# shinobi.net
KiCad netlist of a schematic drawn in EAGLE
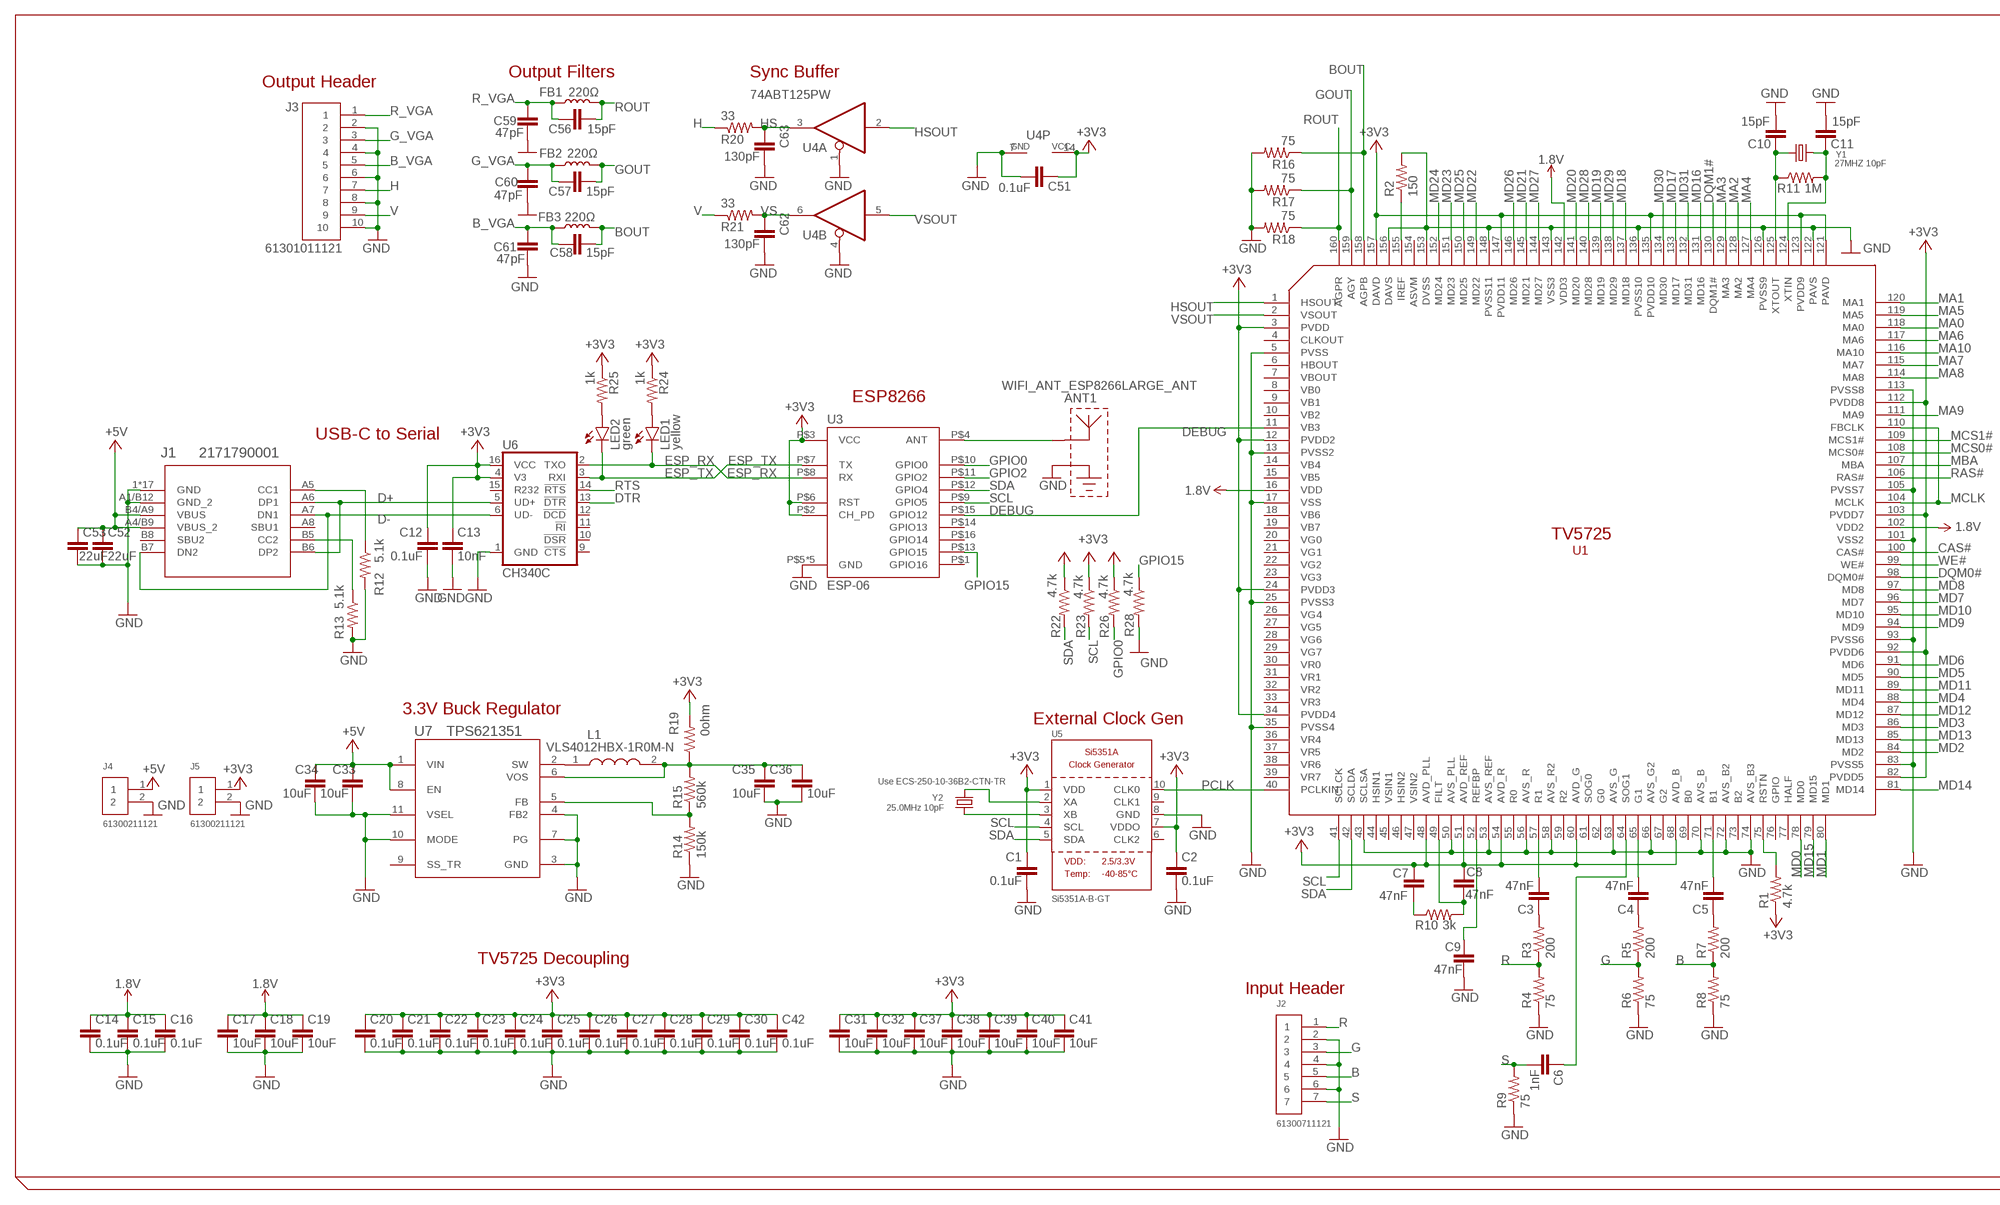
[diagram p0: schematic, sheet 1, part 1 of 2]
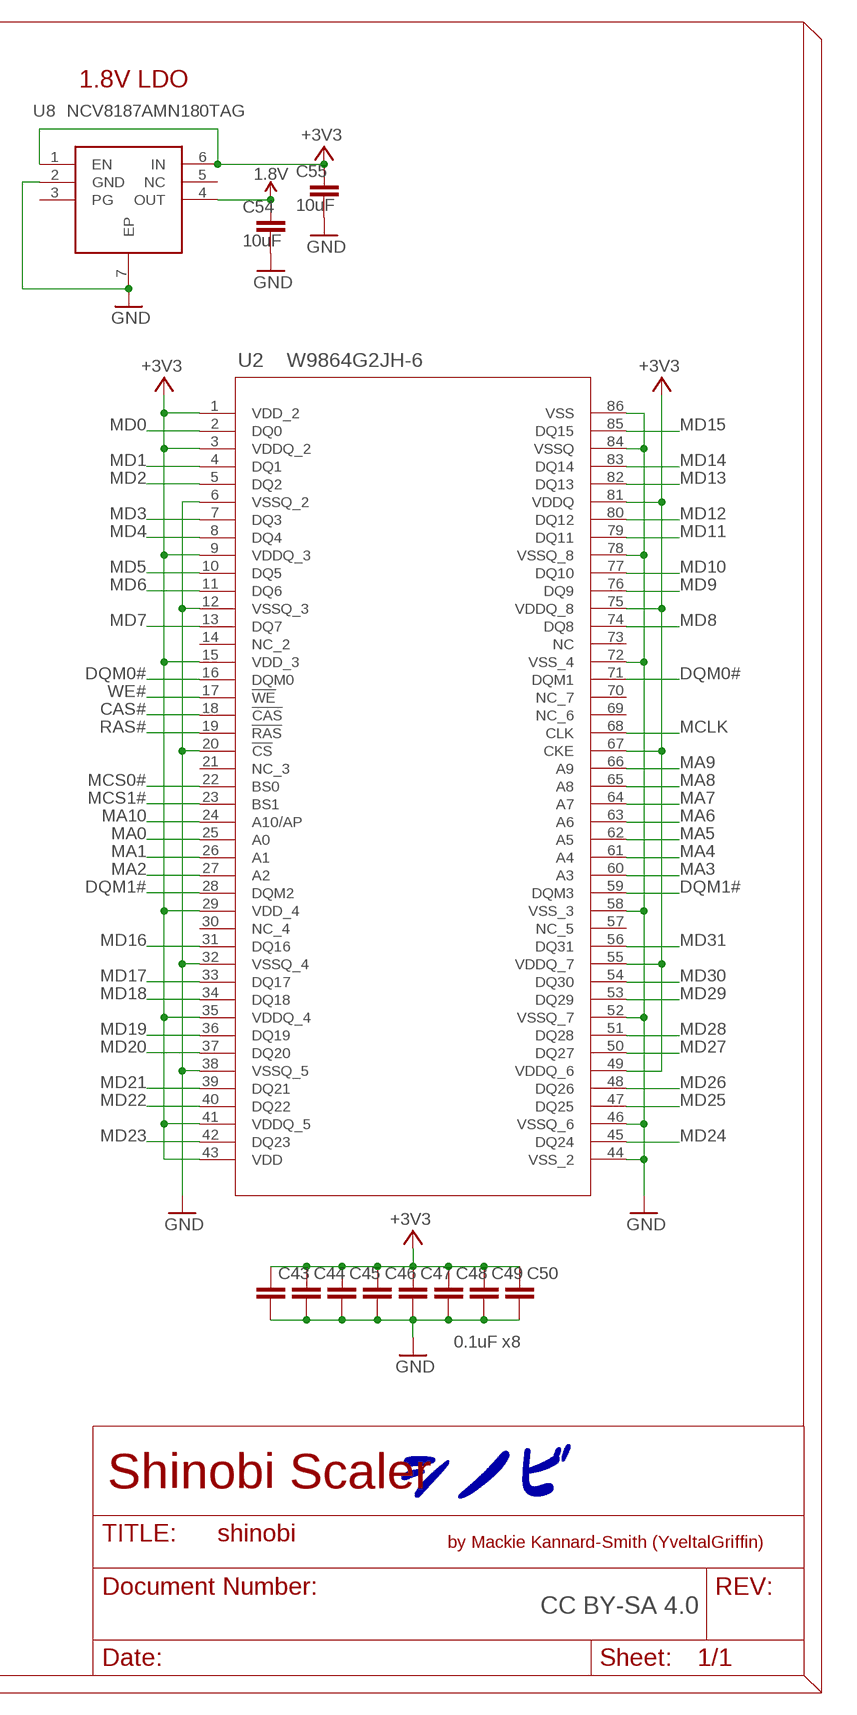
[diagram p1: schematic, sheet 1, part 2 of 2]

(export (version "E")
  (design (tool "Eeschema 10.0.6"))
  (components
    (comp (ref "ANT1")
      (value "WIFI_ANT_ESP8266LARGE_ANT")
      (footprint "eagle-import:ANTENNA")
      (libsource (lib "eagle-import") (part "WIFI_ANT_ESP8266LARGE_ANT"))
    )
    (comp (ref "C1")
      (value "0.1uF")
      (footprint "eagle-import:C0402")
      (libsource (lib "eagle-import") (part "C-USC0402"))
    )
    (comp (ref "C2")
      (value "0.1uF")
      (footprint "eagle-import:C0402")
      (libsource (lib "eagle-import") (part "C-USC0402"))
    )
    (comp (ref "C3")
      (value "47nF")
      (footprint "eagle-import:C0402")
      (libsource (lib "eagle-import") (part "C-USC0402"))
    )
    (comp (ref "C4")
      (value "47nF")
      (footprint "eagle-import:C0402")
      (libsource (lib "eagle-import") (part "C-USC0402"))
    )
    (comp (ref "C5")
      (value "47nF")
      (footprint "eagle-import:C0402")
      (libsource (lib "eagle-import") (part "C-USC0402"))
    )
    (comp (ref "C6")
      (value "1nF")
      (footprint "eagle-import:C0402")
      (libsource (lib "eagle-import") (part "C-USC0402"))
    )
    (comp (ref "C7")
      (value "47nF")
      (footprint "eagle-import:C0402")
      (libsource (lib "eagle-import") (part "C-USC0402"))
    )
    (comp (ref "C8")
      (value "47nF")
      (footprint "eagle-import:C0402")
      (libsource (lib "eagle-import") (part "C-USC0402"))
    )
    (comp (ref "C9")
      (value "47nF")
      (footprint "eagle-import:C0402")
      (libsource (lib "eagle-import") (part "C-USC0402"))
    )
    (comp (ref "C10")
      (value "15pF")
      (footprint "eagle-import:C0402")
      (libsource (lib "eagle-import") (part "C-USC0402"))
    )
    (comp (ref "C11")
      (value "15pF")
      (footprint "eagle-import:C0402")
      (libsource (lib "eagle-import") (part "C-USC0402"))
    )
    (comp (ref "C12")
      (value "0.1uF")
      (footprint "eagle-import:C0402")
      (libsource (lib "eagle-import") (part "C-USC0402"))
    )
    (comp (ref "C13")
      (value "10nF")
      (footprint "eagle-import:C0402")
      (libsource (lib "eagle-import") (part "C-USC0402"))
    )
    (comp (ref "C14")
      (value "0.1uF")
      (footprint "eagle-import:C0402")
      (libsource (lib "eagle-import") (part "C-USC0402"))
    )
    (comp (ref "C15")
      (value "0.1uF")
      (footprint "eagle-import:C0402")
      (libsource (lib "eagle-import") (part "C-USC0402"))
    )
    (comp (ref "C16")
      (value "0.1uF")
      (footprint "eagle-import:C0402")
      (libsource (lib "eagle-import") (part "C-USC0402"))
    )
    (comp (ref "C17")
      (value "10uF")
      (footprint "eagle-import:C0603")
      (libsource (lib "eagle-import") (part "C-USC0603"))
    )
    (comp (ref "C18")
      (value "10uF")
      (footprint "eagle-import:C0603")
      (libsource (lib "eagle-import") (part "C-USC0603"))
    )
    (comp (ref "C19")
      (value "10uF")
      (footprint "eagle-import:C0603")
      (libsource (lib "eagle-import") (part "C-USC0603"))
    )
    (comp (ref "C20")
      (value "0.1uF")
      (footprint "eagle-import:C0402")
      (libsource (lib "eagle-import") (part "C-USC0402"))
    )
    (comp (ref "C21")
      (value "0.1uF")
      (footprint "eagle-import:C0402")
      (libsource (lib "eagle-import") (part "C-USC0402"))
    )
    (comp (ref "C22")
      (value "0.1uF")
      (footprint "eagle-import:C0402")
      (libsource (lib "eagle-import") (part "C-USC0402"))
    )
    (comp (ref "C23")
      (value "0.1uF")
      (footprint "eagle-import:C0402")
      (libsource (lib "eagle-import") (part "C-USC0402"))
    )
    (comp (ref "C24")
      (value "0.1uF")
      (footprint "eagle-import:C0402")
      (libsource (lib "eagle-import") (part "C-USC0402"))
    )
    (comp (ref "C25")
      (value "0.1uF")
      (footprint "eagle-import:C0402")
      (libsource (lib "eagle-import") (part "C-USC0402"))
    )
    (comp (ref "C26")
      (value "0.1uF")
      (footprint "eagle-import:C0402")
      (libsource (lib "eagle-import") (part "C-USC0402"))
    )
    (comp (ref "C27")
      (value "0.1uF")
      (footprint "eagle-import:C0402")
      (libsource (lib "eagle-import") (part "C-USC0402"))
    )
    (comp (ref "C28")
      (value "0.1uF")
      (footprint "eagle-import:C0402")
      (libsource (lib "eagle-import") (part "C-USC0402"))
    )
    (comp (ref "C29")
      (value "0.1uF")
      (footprint "eagle-import:C0402")
      (libsource (lib "eagle-import") (part "C-USC0402"))
    )
    (comp (ref "C30")
      (value "0.1uF")
      (footprint "eagle-import:C0402")
      (libsource (lib "eagle-import") (part "C-USC0402"))
    )
    (comp (ref "C31")
      (value "10uF")
      (footprint "eagle-import:C0603")
      (libsource (lib "eagle-import") (part "C-USC0603"))
    )
    (comp (ref "C32")
      (value "10uF")
      (footprint "eagle-import:C0603")
      (libsource (lib "eagle-import") (part "C-USC0603"))
    )
    (comp (ref "C33")
      (value "10uF")
      (footprint "eagle-import:C0603")
      (libsource (lib "eagle-import") (part "C-USC0603"))
    )
    (comp (ref "C34")
      (value "10uF")
      (footprint "eagle-import:C0603")
      (libsource (lib "eagle-import") (part "C-USC0603"))
    )
    (comp (ref "C35")
      (value "10uF")
      (footprint "eagle-import:C0603")
      (libsource (lib "eagle-import") (part "C-USC0603"))
    )
    (comp (ref "C36")
      (value "10uF")
      (footprint "eagle-import:C0603")
      (libsource (lib "eagle-import") (part "C-USC0603"))
    )
    (comp (ref "C37")
      (value "10uF")
      (footprint "eagle-import:C0603")
      (libsource (lib "eagle-import") (part "C-USC0603"))
    )
    (comp (ref "C38")
      (value "10uF")
      (footprint "eagle-import:C0603")
      (libsource (lib "eagle-import") (part "C-USC0603"))
    )
    (comp (ref "C39")
      (value "10uF")
      (footprint "eagle-import:C0603")
      (libsource (lib "eagle-import") (part "C-USC0603"))
    )
    (comp (ref "C40")
      (value "10uF")
      (footprint "eagle-import:C0603")
      (libsource (lib "eagle-import") (part "C-USC0603"))
    )
    (comp (ref "C41")
      (value "10uF")
      (footprint "eagle-import:C0603")
      (libsource (lib "eagle-import") (part "C-USC0603"))
    )
    (comp (ref "C42")
      (value "0.1uF")
      (footprint "eagle-import:C0402")
      (libsource (lib "eagle-import") (part "C-USC0402"))
    )
    (comp (ref "C43")
      (value "0.1uF")
      (footprint "eagle-import:C0402")
      (libsource (lib "eagle-import") (part "C-USC0402"))
    )
    (comp (ref "C44")
      (value "0.1uF")
      (footprint "eagle-import:C0402")
      (libsource (lib "eagle-import") (part "C-USC0402"))
    )
    (comp (ref "C45")
      (value "0.1uF")
      (footprint "eagle-import:C0402")
      (libsource (lib "eagle-import") (part "C-USC0402"))
    )
    (comp (ref "C46")
      (value "0.1uF")
      (footprint "eagle-import:C0402")
      (libsource (lib "eagle-import") (part "C-USC0402"))
    )
    (comp (ref "C47")
      (value "0.1uF")
      (footprint "eagle-import:C0402")
      (libsource (lib "eagle-import") (part "C-USC0402"))
    )
    (comp (ref "C48")
      (value "0.1uF")
      (footprint "eagle-import:C0402")
      (libsource (lib "eagle-import") (part "C-USC0402"))
    )
    (comp (ref "C49")
      (value "0.1uF")
      (footprint "eagle-import:C0402")
      (libsource (lib "eagle-import") (part "C-USC0402"))
    )
    (comp (ref "C50")
      (value "0.1uF")
      (footprint "eagle-import:C0402")
      (libsource (lib "eagle-import") (part "C-USC0402"))
    )
    (comp (ref "C51")
      (value "0.1uF")
      (footprint "eagle-import:C0402")
      (libsource (lib "eagle-import") (part "C-USC0402"))
    )
    (comp (ref "C52")
      (value "22uF")
      (footprint "eagle-import:C0805")
      (libsource (lib "eagle-import") (part "C-USC0805"))
    )
    (comp (ref "C53")
      (value "22uF")
      (footprint "eagle-import:C0805")
      (libsource (lib "eagle-import") (part "C-USC0805"))
    )
    (comp (ref "C54")
      (value "10uF")
      (footprint "eagle-import:C0603")
      (libsource (lib "eagle-import") (part "C-USC0603"))
    )
    (comp (ref "C55")
      (value "10uF")
      (footprint "eagle-import:C0603")
      (libsource (lib "eagle-import") (part "C-USC0603"))
    )
    (comp (ref "C56")
      (value "15pF")
      (footprint "eagle-import:C0402")
      (libsource (lib "eagle-import") (part "C-USC0402"))
    )
    (comp (ref "C57")
      (value "15pF")
      (footprint "eagle-import:C0402")
      (libsource (lib "eagle-import") (part "C-USC0402"))
    )
    (comp (ref "C58")
      (value "15pF")
      (footprint "eagle-import:C0402")
      (libsource (lib "eagle-import") (part "C-USC0402"))
    )
    (comp (ref "C59")
      (value "47pF")
      (footprint "eagle-import:C0402")
      (libsource (lib "eagle-import") (part "C-USC0402"))
    )
    (comp (ref "C60")
      (value "47pF")
      (footprint "eagle-import:C0402")
      (libsource (lib "eagle-import") (part "C-USC0402"))
    )
    (comp (ref "C61")
      (value "47pF")
      (footprint "eagle-import:C0402")
      (libsource (lib "eagle-import") (part "C-USC0402"))
    )
    (comp (ref "C62")
      (value "130pF")
      (footprint "eagle-import:C0402")
      (libsource (lib "eagle-import") (part "C-USC0402"))
    )
    (comp (ref "C63")
      (value "130pF")
      (footprint "eagle-import:C0402")
      (libsource (lib "eagle-import") (part "C-USC0402"))
    )
    (comp (ref "FB1")
      (value "220Ω")
      (footprint "eagle-import:R0402")
      (libsource (lib "eagle-import") (part "L0402"))
    )
    (comp (ref "FB2")
      (value "220Ω")
      (footprint "eagle-import:R0402")
      (libsource (lib "eagle-import") (part "L0402"))
    )
    (comp (ref "FB3")
      (value "220Ω")
      (footprint "eagle-import:R0402")
      (libsource (lib "eagle-import") (part "L0402"))
    )
    (comp (ref "J1")
      (value "2171790001")
      (footprint "eagle-import:2171790001_MOL")
      (fields (field (name "COPYRIGHT") "Copyright (C) 2022 Ultra Librarian. All rights reserved."))
      (libsource (lib "eagle-import") (part "2171790001"))
    )
    (comp (ref "J2")
      (value "61300711121")
      (footprint "eagle-import:61300711121")
      (fields
        (field (name "DIGI_KEY_PART_NUMBER") "732-5320-ND")
        (field (name "MANUFACTURER") "Wurth Electronics Inc.")
        (field (name "CREATED_BY") "PCBLayout.com")
      )
      (libsource (lib "eagle-import") (part "61300711121"))
    )
    (comp (ref "J3")
      (value "61301011121")
      (footprint "eagle-import:61301011121")
      (fields
        (field (name "DIGIKEY_PART_NUMBER") "732-2670-ND")
        (field (name "MANUFACTURER") "Wurth Electronics Inc.")
        (field (name "CREATED_BY") "PCBLayout.com")
      )
      (libsource (lib "eagle-import") (part "61301011121"))
    )
    (comp (ref "J4")
      (value "61300211121")
      (footprint "eagle-import:61300211121")
      (fields
        (field (name "DIGI_KEY_PART_NUMBER") "732-5315-ND")
        (field (name "MANUFACTURER") "Wurth Electronics Inc.")
        (field (name "CREATED_BY") "PCBLayout.com")
      )
      (libsource (lib "eagle-import") (part "61300211121"))
    )
    (comp (ref "J5")
      (value "61300211121")
      (footprint "eagle-import:61300211121")
      (fields
        (field (name "DIGI_KEY_PART_NUMBER") "732-5315-ND")
        (field (name "MANUFACTURER") "Wurth Electronics Inc.")
        (field (name "CREATED_BY") "PCBLayout.com")
      )
      (libsource (lib "eagle-import") (part "61300211121"))
    )
    (comp (ref "L1")
      (value "VLS4012HBX-1R0M-N")
      (footprint "eagle-import:VLS4012")
      (fields (field (name "MOUSER_PART_NUMBER") "810-VLS4012HBX1R0M-N"))
      (libsource (lib "eagle-import") (part "VLS4012HBX-1R0M-N"))
    )
    (comp (ref "LED1")
      (value "yellow")
      (footprint "eagle-import:CHIP-LED0603")
      (libsource (lib "eagle-import") (part "LEDCHIP-LED0603"))
    )
    (comp (ref "LED2")
      (value "green")
      (footprint "eagle-import:CHIP-LED0603")
      (libsource (lib "eagle-import") (part "LEDCHIP-LED0603"))
    )
    (comp (ref "R1")
      (value "4.7k")
      (footprint "eagle-import:R0402")
      (libsource (lib "eagle-import") (part "R-US_R0402"))
    )
    (comp (ref "R2")
      (value "150")
      (footprint "eagle-import:R0402")
      (libsource (lib "eagle-import") (part "R-US_R0402"))
    )
    (comp (ref "R3")
      (value "200")
      (footprint "eagle-import:R0402")
      (libsource (lib "eagle-import") (part "R-US_R0402"))
    )
    (comp (ref "R4")
      (value "75")
      (footprint "eagle-import:R0402")
      (libsource (lib "eagle-import") (part "R-US_R0402"))
    )
    (comp (ref "R5")
      (value "200")
      (footprint "eagle-import:R0402")
      (libsource (lib "eagle-import") (part "R-US_R0402"))
    )
    (comp (ref "R6")
      (value "75")
      (footprint "eagle-import:R0402")
      (libsource (lib "eagle-import") (part "R-US_R0402"))
    )
    (comp (ref "R7")
      (value "200")
      (footprint "eagle-import:R0402")
      (libsource (lib "eagle-import") (part "R-US_R0402"))
    )
    (comp (ref "R8")
      (value "75")
      (footprint "eagle-import:R0402")
      (libsource (lib "eagle-import") (part "R-US_R0402"))
    )
    (comp (ref "R9")
      (value "75")
      (footprint "eagle-import:R0402")
      (libsource (lib "eagle-import") (part "R-US_R0402"))
    )
    (comp (ref "R10")
      (value "3k")
      (footprint "eagle-import:R0402")
      (libsource (lib "eagle-import") (part "R-US_R0402"))
    )
    (comp (ref "R11")
      (value "1M")
      (footprint "eagle-import:R0402")
      (libsource (lib "eagle-import") (part "R-US_R0402"))
    )
    (comp (ref "R12")
      (value "5.1k")
      (footprint "eagle-import:R0402")
      (libsource (lib "eagle-import") (part "R-US_R0402"))
    )
    (comp (ref "R13")
      (value "5.1k")
      (footprint "eagle-import:R0402")
      (libsource (lib "eagle-import") (part "R-US_R0402"))
    )
    (comp (ref "R14")
      (value "150k")
      (footprint "eagle-import:R0402")
      (libsource (lib "eagle-import") (part "R-US_R0402"))
    )
    (comp (ref "R15")
      (value "560k")
      (footprint "eagle-import:R0402")
      (libsource (lib "eagle-import") (part "R-US_R0402"))
    )
    (comp (ref "R16")
      (value "75")
      (footprint "eagle-import:R0402")
      (libsource (lib "eagle-import") (part "R-US_R0402"))
    )
    (comp (ref "R17")
      (value "75")
      (footprint "eagle-import:R0402")
      (libsource (lib "eagle-import") (part "R-US_R0402"))
    )
    (comp (ref "R18")
      (value "75")
      (footprint "eagle-import:R0402")
      (libsource (lib "eagle-import") (part "R-US_R0402"))
    )
    (comp (ref "R19")
      (value "0ohm")
      (footprint "eagle-import:R0805")
      (libsource (lib "eagle-import") (part "R-US_R0805"))
    )
    (comp (ref "R20")
      (value "33")
      (footprint "eagle-import:R0402")
      (libsource (lib "eagle-import") (part "R-US_R0402"))
    )
    (comp (ref "R21")
      (value "33")
      (footprint "eagle-import:R0402")
      (libsource (lib "eagle-import") (part "R-US_R0402"))
    )
    (comp (ref "R22")
      (value "4.7k")
      (footprint "eagle-import:R0402")
      (libsource (lib "eagle-import") (part "R-US_R0402"))
    )
    (comp (ref "R23")
      (value "4.7k")
      (footprint "eagle-import:R0402")
      (libsource (lib "eagle-import") (part "R-US_R0402"))
    )
    (comp (ref "R24")
      (value "1k")
      (footprint "eagle-import:R0402")
      (libsource (lib "eagle-import") (part "R-US_R0402"))
    )
    (comp (ref "R25")
      (value "1k")
      (footprint "eagle-import:R0402")
      (libsource (lib "eagle-import") (part "R-US_R0402"))
    )
    (comp (ref "R26")
      (value "4.7k")
      (footprint "eagle-import:R0402")
      (libsource (lib "eagle-import") (part "R-US_R0402"))
    )
    (comp (ref "R28")
      (value "4.7k")
      (footprint "eagle-import:R0402")
      (libsource (lib "eagle-import") (part "R-US_R0402"))
    )
    (comp (ref "U1")
      (value "TV5725")
      (footprint "eagle-import:PQFP160")
      (libsource (lib "eagle-import") (part "TV5725"))
    )
    (comp (ref "U2")
      (value "W9864G2JH-6")
      (footprint "eagle-import:WIN_TSOP-86_WIN")
      (fields (field (name "COPYRIGHT") "Copyright (C) 2022 Ultra Librarian. All rights reserved."))
      (libsource (lib "eagle-import") (part "W9864G2JH-6"))
    )
    (comp (ref "U3")
      (value "ESP-06")
      (footprint "eagle-import:ESP-06")
      (libsource (lib "eagle-import") (part "ESP-06"))
    )
    (comp (ref "U4")
      (value "74ABT125PW")
      (footprint "eagle-import:TSSOP14")
      (libsource (lib "eagle-import") (part "74125PWABT"))
    )
    (comp (ref "U5")
      (value "Si5351A-B-GT")
      (footprint "eagle-import:MSOP10")
      (libsource (lib "eagle-import") (part "SI5351A"))
    )
    (comp (ref "U6")
      (value "CH340C")
      (footprint "eagle-import:SO016")
      (libsource (lib "eagle-import") (part "CH340C"))
    )
    (comp (ref "U7")
      (value "TPS621351")
      (footprint "eagle-import:RGX0011A")
      (fields
        (field (name "MANUFACTURER") "Texas Instruments")
        (field (name "MANUFACTURER_PART_NUMBER") "TPS621351RGXR")
      )
      (libsource (lib "eagle-import") (part "TPS621351RGXR"))
    )
    (comp (ref "U8")
      (value "NCV8187AMN180TAG")
      (footprint "eagle-import:SON95P300X300X95-7N")
      (fields (field (name "MOUSER_PART_NUMBER") "863-NCV8187AMN180TAG"))
      (libsource (lib "eagle-import") (part "NCV8187AMN180TAG"))
    )
    (comp (ref "Y1")
      (value "27MHZ 10pF")
      (footprint "eagle-import:CRYSTAL_2.5X2")
      (libsource (lib "eagle-import") (part "CRYSTAL2.5X2.0"))
    )
    (comp (ref "Y2")
      (value "25.0MHz 10pF")
      (footprint "eagle-import:CRYSTAL_2.5X2")
      (libsource (lib "eagle-import") (part "CRYSTAL2.5X2.0"))
    )
  )
  (nets
    (net (code "1") (name "+3V3") (class "Default")
      (node (ref "C1") (pin "1") (pinfunction "1_1") (pintype "passive"))
      (node (ref "C12") (pin "1") (pinfunction "1_1") (pintype "passive"))
      (node (ref "C13") (pin "1") (pinfunction "1_1") (pintype "passive"))
      (node (ref "C2") (pin "1") (pinfunction "1_1") (pintype "passive"))
      (node (ref "C20") (pin "1") (pinfunction "1_1") (pintype "passive"))
      (node (ref "C21") (pin "1") (pinfunction "1_1") (pintype "passive"))
      (node (ref "C22") (pin "1") (pinfunction "1_1") (pintype "passive"))
      (node (ref "C23") (pin "1") (pinfunction "1_1") (pintype "passive"))
      (node (ref "C24") (pin "1") (pinfunction "1_1") (pintype "passive"))
      (node (ref "C25") (pin "1") (pinfunction "1_1") (pintype "passive"))
      (node (ref "C26") (pin "1") (pinfunction "1_1") (pintype "passive"))
      (node (ref "C27") (pin "1") (pinfunction "1_1") (pintype "passive"))
      (node (ref "C28") (pin "1") (pinfunction "1_1") (pintype "passive"))
      (node (ref "C29") (pin "1") (pinfunction "1_1") (pintype "passive"))
      (node (ref "C30") (pin "1") (pinfunction "1_1") (pintype "passive"))
      (node (ref "C31") (pin "1") (pinfunction "1_1") (pintype "passive"))
      (node (ref "C32") (pin "1") (pinfunction "1_1") (pintype "passive"))
      (node (ref "C37") (pin "1") (pinfunction "1_1") (pintype "passive"))
      (node (ref "C38") (pin "1") (pinfunction "1_1") (pintype "passive"))
      (node (ref "C39") (pin "1") (pinfunction "1_1") (pintype "passive"))
      (node (ref "C40") (pin "1") (pinfunction "1_1") (pintype "passive"))
      (node (ref "C41") (pin "1") (pinfunction "1_1") (pintype "passive"))
      (node (ref "C42") (pin "1") (pinfunction "1_1") (pintype "passive"))
      (node (ref "C43") (pin "1") (pinfunction "1_1") (pintype "passive"))
      (node (ref "C44") (pin "1") (pinfunction "1_1") (pintype "passive"))
      (node (ref "C45") (pin "1") (pinfunction "1_1") (pintype "passive"))
      (node (ref "C46") (pin "1") (pinfunction "1_1") (pintype "passive"))
      (node (ref "C47") (pin "1") (pinfunction "1_1") (pintype "passive"))
      (node (ref "C48") (pin "1") (pinfunction "1_1") (pintype "passive"))
      (node (ref "C49") (pin "1") (pinfunction "1_1") (pintype "passive"))
      (node (ref "C50") (pin "1") (pinfunction "1_1") (pintype "passive"))
      (node (ref "C51") (pin "1") (pinfunction "1_1") (pintype "passive"))
      (node (ref "C55") (pin "1") (pinfunction "1_1") (pintype "passive"))
      (node (ref "C7") (pin "2") (pinfunction "2_2") (pintype "passive"))
      (node (ref "C8") (pin "2") (pinfunction "2_2") (pintype "passive"))
      (node (ref "J5") (pin "1") (pinfunction "1_1") (pintype "passive"))
      (node (ref "R1") (pin "1") (pinfunction "1_1") (pintype "passive"))
      (node (ref "R19") (pin "2") (pinfunction "2_2") (pintype "passive"))
      (node (ref "R22") (pin "1") (pinfunction "1_1") (pintype "passive"))
      (node (ref "R23") (pin "1") (pinfunction "1_1") (pintype "passive"))
      (node (ref "R24") (pin "1") (pinfunction "1_1") (pintype "passive"))
      (node (ref "R25") (pin "1") (pinfunction "1_1") (pintype "passive"))
      (node (ref "R26") (pin "1") (pinfunction "1_1") (pintype "passive"))
      (node (ref "U1") (pin "103") (pinfunction "PVDD7_103") (pintype "bidirectional"))
      (node (ref "U1") (pin "112") (pinfunction "PVDD8_112") (pintype "bidirectional"))
      (node (ref "U1") (pin "12") (pinfunction "PVDD2_12") (pintype "bidirectional"))
      (node (ref "U1") (pin "121") (pinfunction "PAVD_121") (pintype "bidirectional"))
      (node (ref "U1") (pin "123") (pinfunction "PVDD9_123") (pintype "bidirectional"))
      (node (ref "U1") (pin "135") (pinfunction "PVDD10_135") (pintype "bidirectional"))
      (node (ref "U1") (pin "147") (pinfunction "PVDD11_147") (pintype "bidirectional"))
      (node (ref "U1") (pin "157") (pinfunction "DAVD_157") (pintype "bidirectional"))
      (node (ref "U1") (pin "24") (pinfunction "PVDD3_24") (pintype "bidirectional"))
      (node (ref "U1") (pin "3") (pinfunction "PVDD_3") (pintype "bidirectional"))
      (node (ref "U1") (pin "34") (pinfunction "PVDD4_34") (pintype "bidirectional"))
      (node (ref "U1") (pin "48") (pinfunction "AVD_PLL_48") (pintype "bidirectional"))
      (node (ref "U1") (pin "51") (pinfunction "AVD_REF_51") (pintype "bidirectional"))
      (node (ref "U1") (pin "54") (pinfunction "AVD_R_54") (pintype "bidirectional"))
      (node (ref "U1") (pin "60") (pinfunction "AVD_G_60") (pintype "bidirectional"))
      (node (ref "U1") (pin "68") (pinfunction "AVD_B_68") (pintype "bidirectional"))
      (node (ref "U1") (pin "82") (pinfunction "PVDD5_82") (pintype "bidirectional"))
      (node (ref "U1") (pin "92") (pinfunction "PVDD6_92") (pintype "bidirectional"))
      (node (ref "U2") (pin "1") (pinfunction "VDD_2_1") (pintype "power_in"))
      (node (ref "U2") (pin "15") (pinfunction "VDD_3_15") (pintype "power_in"))
      (node (ref "U2") (pin "29") (pinfunction "VDD_4_29") (pintype "power_in"))
      (node (ref "U2") (pin "3") (pinfunction "VDDQ_2_3") (pintype "power_in"))
      (node (ref "U2") (pin "35") (pinfunction "VDDQ_4_35") (pintype "power_in"))
      (node (ref "U2") (pin "41") (pinfunction "VDDQ_5_41") (pintype "power_in"))
      (node (ref "U2") (pin "43") (pinfunction "VDD_43") (pintype "power_in"))
      (node (ref "U2") (pin "49") (pinfunction "VDDQ_6_49") (pintype "power_in"))
      (node (ref "U2") (pin "55") (pinfunction "VDDQ_7_55") (pintype "power_in"))
      (node (ref "U2") (pin "67") (pinfunction "CKE_67") (pintype "passive"))
      (node (ref "U2") (pin "75") (pinfunction "VDDQ_8_75") (pintype "power_in"))
      (node (ref "U2") (pin "81") (pinfunction "VDDQ_81") (pintype "power_in"))
      (node (ref "U2") (pin "9") (pinfunction "VDDQ_3_9") (pintype "power_in"))
      (node (ref "U3") (pin "P$2") (pinfunction "CH_PD_P$2") (pintype "bidirectional"))
      (node (ref "U3") (pin "P$3") (pinfunction "VCC_P$3") (pintype "bidirectional"))
      (node (ref "U3") (pin "P$6") (pinfunction "RST_P$6") (pintype "bidirectional"))
      (node (ref "U4") (pin "14") (pinfunction "VCC_14") (pintype "power_in"))
      (node (ref "U5") (pin "1") (pinfunction "VDD_1") (pintype "power_in"))
      (node (ref "U5") (pin "7") (pinfunction "VDDO_7") (pintype "power_in"))
      (node (ref "U6") (pin "16") (pinfunction "VCC_16") (pintype "bidirectional"))
      (node (ref "U6") (pin "4") (pinfunction "V3_4") (pintype "bidirectional"))
      (node (ref "U8") (pin "1") (pinfunction "EN_1") (pintype "bidirectional"))
      (node (ref "U8") (pin "6") (pinfunction "IN_6") (pintype "bidirectional"))
    )
    (net (code "2") (name "+5V") (class "Default")
      (node (ref "C33") (pin "1") (pinfunction "1_1") (pintype "passive"))
      (node (ref "C34") (pin "1") (pinfunction "1_1") (pintype "passive"))
      (node (ref "C52") (pin "1") (pinfunction "1_1") (pintype "passive"))
      (node (ref "C53") (pin "1") (pinfunction "1_1") (pintype "passive"))
      (node (ref "J1") (pin "A4/B9") (pinfunction "VBUS_2_A4/B9") (pintype "power_in"))
      (node (ref "J1") (pin "B4/A9") (pinfunction "VBUS_B4/A9") (pintype "power_in"))
      (node (ref "J4") (pin "1") (pinfunction "1_1") (pintype "passive"))
      (node (ref "U7") (pin "1") (pinfunction "VIN_1") (pintype "power_in"))
      (node (ref "U7") (pin "8") (pinfunction "EN_8") (pintype "input"))
    )
    (net (code "3") (name "/B") (class "Default")
      (node (ref "J2") (pin "5") (pinfunction "5_5") (pintype "passive"))
      (node (ref "R7") (pin "1") (pinfunction "1_1") (pintype "passive"))
      (node (ref "R8") (pin "2") (pinfunction "2_2") (pintype "passive"))
    )
    (net (code "4") (name "/BOUT") (class "Default")
      (node (ref "C58") (pin "1") (pinfunction "1_1") (pintype "passive"))
      (node (ref "FB3") (pin "1") (pinfunction "P$1_1") (pintype "bidirectional"))
      (node (ref "R16") (pin "1") (pinfunction "1_1") (pintype "passive"))
      (node (ref "U1") (pin "158") (pinfunction "AGPB_158") (pintype "bidirectional"))
    )
    (net (code "5") (name "/B_VGA") (class "Default")
      (node (ref "C58") (pin "2") (pinfunction "2_2") (pintype "passive"))
      (node (ref "C61") (pin "1") (pinfunction "1_1") (pintype "passive"))
      (node (ref "FB3") (pin "2") (pinfunction "P$2_2") (pintype "bidirectional"))
      (node (ref "J3") (pin "5") (pinfunction "5_5") (pintype "passive"))
    )
    (net (code "6") (name "/CAS#") (class "Default")
      (node (ref "U1") (pin "100") (pinfunction "CAS#_100") (pintype "bidirectional"))
      (node (ref "U2") (pin "18") (pinfunction "~{CAS}_18") (pintype "passive"))
    )
    (net (code "7") (name "/D+") (class "Default")
      (node (ref "J1") (pin "A6") (pinfunction "DP1_A6") (pintype "bidirectional"))
      (node (ref "J1") (pin "B6") (pinfunction "DP2_B6") (pintype "bidirectional"))
      (node (ref "U6") (pin "5") (pinfunction "UD+_5") (pintype "bidirectional"))
    )
    (net (code "8") (name "/D-") (class "Default")
      (node (ref "J1") (pin "A7") (pinfunction "DN1_A7") (pintype "bidirectional"))
      (node (ref "J1") (pin "B7") (pinfunction "DN2_B7") (pintype "bidirectional"))
      (node (ref "U6") (pin "6") (pinfunction "UD-_6") (pintype "bidirectional"))
    )
    (net (code "9") (name "/DEBUG") (class "Default")
      (node (ref "U1") (pin "11") (pinfunction "VB3_11") (pintype "bidirectional"))
      (node (ref "U3") (pin "P$15") (pinfunction "GPIO12_P$15") (pintype "bidirectional"))
    )
    (net (code "10") (name "/DQM0#") (class "Default")
      (node (ref "U1") (pin "98") (pinfunction "DQM0#_98") (pintype "bidirectional"))
      (node (ref "U2") (pin "16") (pinfunction "DQM0_16") (pintype "bidirectional"))
      (node (ref "U2") (pin "71") (pinfunction "DQM1_71") (pintype "bidirectional"))
    )
    (net (code "11") (name "/DQM1#") (class "Default")
      (node (ref "U1") (pin "130") (pinfunction "DQM1#_130") (pintype "bidirectional"))
      (node (ref "U2") (pin "28") (pinfunction "DQM2_28") (pintype "bidirectional"))
      (node (ref "U2") (pin "59") (pinfunction "DQM3_59") (pintype "bidirectional"))
    )
    (net (code "12") (name "/DTR") (class "Default")
      (node (ref "U6") (pin "13") (pinfunction "~{DTR}_13") (pintype "bidirectional"))
    )
    (net (code "13") (name "/ESP_RX") (class "Default")
      (node (ref "LED1") (pin "C") (pinfunction "C_C") (pintype "passive"))
      (node (ref "U3") (pin "P$8") (pinfunction "RX_P$8") (pintype "bidirectional"))
      (node (ref "U6") (pin "2") (pinfunction "TXO_2") (pintype "bidirectional"))
    )
    (net (code "14") (name "/ESP_TX") (class "Default")
      (node (ref "LED2") (pin "C") (pinfunction "C_C") (pintype "passive"))
      (node (ref "U3") (pin "P$7") (pinfunction "TX_P$7") (pintype "bidirectional"))
      (node (ref "U6") (pin "3") (pinfunction "RXI_3") (pintype "bidirectional"))
    )
    (net (code "15") (name "/G") (class "Default")
      (node (ref "J2") (pin "3") (pinfunction "3_3") (pintype "passive"))
      (node (ref "R5") (pin "1") (pinfunction "1_1") (pintype "passive"))
      (node (ref "R6") (pin "2") (pinfunction "2_2") (pintype "passive"))
    )
    (net (code "16") (name "/GOUT") (class "Default")
      (node (ref "C57") (pin "1") (pinfunction "1_1") (pintype "passive"))
      (node (ref "FB2") (pin "1") (pinfunction "P$1_1") (pintype "bidirectional"))
      (node (ref "R17") (pin "1") (pinfunction "1_1") (pintype "passive"))
      (node (ref "U1") (pin "159") (pinfunction "AGY_159") (pintype "bidirectional"))
    )
    (net (code "17") (name "/GPIO0") (class "Default")
      (node (ref "R26") (pin "2") (pinfunction "2_2") (pintype "passive"))
      (node (ref "U3") (pin "P$10") (pinfunction "GPIO0_P$10") (pintype "bidirectional"))
    )
    (net (code "18") (name "/GPIO2") (class "Default")
      (node (ref "U3") (pin "P$11") (pinfunction "GPIO2_P$11") (pintype "bidirectional"))
    )
    (net (code "19") (name "/GPIO15") (class "Default")
      (node (ref "R28") (pin "1") (pinfunction "1_1") (pintype "passive"))
      (node (ref "U3") (pin "P$13") (pinfunction "GPIO15_P$13") (pintype "bidirectional"))
    )
    (net (code "20") (name "/G_VGA") (class "Default")
      (node (ref "C57") (pin "2") (pinfunction "2_2") (pintype "passive"))
      (node (ref "C60") (pin "1") (pinfunction "1_1") (pintype "passive"))
      (node (ref "FB2") (pin "2") (pinfunction "P$2_2") (pintype "bidirectional"))
      (node (ref "J3") (pin "3") (pinfunction "3_3") (pintype "passive"))
    )
    (net (code "21") (name "/H") (class "Default")
      (node (ref "J3") (pin "7") (pinfunction "7_7") (pintype "passive"))
      (node (ref "R20") (pin "1") (pinfunction "1_1") (pintype "passive"))
    )
    (net (code "22") (name "/HS") (class "Default")
      (node (ref "C63") (pin "1") (pinfunction "1_1") (pintype "passive"))
      (node (ref "R20") (pin "2") (pinfunction "2_2") (pintype "passive"))
      (node (ref "U4") (pin "3") (pinfunction "O_3") (pintype "tri_state"))
    )
    (net (code "23") (name "/HSOUT") (class "Default")
      (node (ref "U1") (pin "1") (pinfunction "HSOUT_1") (pintype "bidirectional"))
      (node (ref "U4") (pin "2") (pinfunction "I_2") (pintype "input"))
    )
    (net (code "24") (name "/MA0") (class "Default")
      (node (ref "U1") (pin "118") (pinfunction "MA0_118") (pintype "bidirectional"))
      (node (ref "U2") (pin "25") (pinfunction "A0_25") (pintype "input"))
    )
    (net (code "25") (name "/MA1") (class "Default")
      (node (ref "U1") (pin "120") (pinfunction "MA1_120") (pintype "bidirectional"))
      (node (ref "U2") (pin "26") (pinfunction "A1_26") (pintype "input"))
    )
    (net (code "26") (name "/MA2") (class "Default")
      (node (ref "U1") (pin "128") (pinfunction "MA2_128") (pintype "bidirectional"))
      (node (ref "U2") (pin "27") (pinfunction "A2_27") (pintype "input"))
    )
    (net (code "27") (name "/MA3") (class "Default")
      (node (ref "U1") (pin "129") (pinfunction "MA3_129") (pintype "bidirectional"))
      (node (ref "U2") (pin "60") (pinfunction "A3_60") (pintype "input"))
    )
    (net (code "28") (name "/MA4") (class "Default")
      (node (ref "U1") (pin "127") (pinfunction "MA4_127") (pintype "bidirectional"))
      (node (ref "U2") (pin "61") (pinfunction "A4_61") (pintype "input"))
    )
    (net (code "29") (name "/MA5") (class "Default")
      (node (ref "U1") (pin "119") (pinfunction "MA5_119") (pintype "bidirectional"))
      (node (ref "U2") (pin "62") (pinfunction "A5_62") (pintype "input"))
    )
    (net (code "30") (name "/MA6") (class "Default")
      (node (ref "U1") (pin "117") (pinfunction "MA6_117") (pintype "bidirectional"))
      (node (ref "U2") (pin "63") (pinfunction "A6_63") (pintype "input"))
    )
    (net (code "31") (name "/MA7") (class "Default")
      (node (ref "U1") (pin "115") (pinfunction "MA7_115") (pintype "bidirectional"))
      (node (ref "U2") (pin "64") (pinfunction "A7_64") (pintype "input"))
    )
    (net (code "32") (name "/MA8") (class "Default")
      (node (ref "U1") (pin "114") (pinfunction "MA8_114") (pintype "bidirectional"))
      (node (ref "U2") (pin "65") (pinfunction "A8_65") (pintype "input"))
    )
    (net (code "33") (name "/MA9") (class "Default")
      (node (ref "U1") (pin "111") (pinfunction "MA9_111") (pintype "bidirectional"))
      (node (ref "U2") (pin "66") (pinfunction "A9_66") (pintype "input"))
    )
    (net (code "34") (name "/MA10") (class "Default")
      (node (ref "U1") (pin "116") (pinfunction "MA10_116") (pintype "bidirectional"))
      (node (ref "U2") (pin "24") (pinfunction "A10/AP_24") (pintype "input"))
    )
    (net (code "35") (name "/MBA") (class "Default")
      (node (ref "U1") (pin "107") (pinfunction "MBA_107") (pintype "bidirectional"))
    )
    (net (code "36") (name "/MCLK") (class "Default")
      (node (ref "U1") (pin "104") (pinfunction "MCLK_104") (pintype "bidirectional"))
      (node (ref "U1") (pin "110") (pinfunction "FBCLK_110") (pintype "bidirectional"))
      (node (ref "U2") (pin "68") (pinfunction "CLK_68") (pintype "input"))
    )
    (net (code "37") (name "/MCS0#") (class "Default")
      (node (ref "U1") (pin "108") (pinfunction "MCS0#_108") (pintype "bidirectional"))
      (node (ref "U2") (pin "22") (pinfunction "BS0_22") (pintype "passive"))
    )
    (net (code "38") (name "/MCS1#") (class "Default")
      (node (ref "U1") (pin "109") (pinfunction "MCS1#_109") (pintype "bidirectional"))
      (node (ref "U2") (pin "23") (pinfunction "BS1_23") (pintype "passive"))
    )
    (net (code "39") (name "/MD0") (class "Default")
      (node (ref "U1") (pin "78") (pinfunction "MD0_78") (pintype "bidirectional"))
      (node (ref "U2") (pin "2") (pinfunction "DQ0_2") (pintype "bidirectional"))
    )
    (net (code "40") (name "/MD1") (class "Default")
      (node (ref "U1") (pin "80") (pinfunction "MD1_80") (pintype "bidirectional"))
      (node (ref "U2") (pin "4") (pinfunction "DQ1_4") (pintype "bidirectional"))
    )
    (net (code "41") (name "/MD2") (class "Default")
      (node (ref "U1") (pin "84") (pinfunction "MD2_84") (pintype "bidirectional"))
      (node (ref "U2") (pin "5") (pinfunction "DQ2_5") (pintype "bidirectional"))
    )
    (net (code "42") (name "/MD3") (class "Default")
      (node (ref "U1") (pin "86") (pinfunction "MD3_86") (pintype "bidirectional"))
      (node (ref "U2") (pin "7") (pinfunction "DQ3_7") (pintype "bidirectional"))
    )
    (net (code "43") (name "/MD4") (class "Default")
      (node (ref "U1") (pin "88") (pinfunction "MD4_88") (pintype "bidirectional"))
      (node (ref "U2") (pin "8") (pinfunction "DQ4_8") (pintype "bidirectional"))
    )
    (net (code "44") (name "/MD5") (class "Default")
      (node (ref "U1") (pin "90") (pinfunction "MD5_90") (pintype "bidirectional"))
      (node (ref "U2") (pin "10") (pinfunction "DQ5_10") (pintype "bidirectional"))
    )
    (net (code "45") (name "/MD6") (class "Default")
      (node (ref "U1") (pin "91") (pinfunction "MD6_91") (pintype "bidirectional"))
      (node (ref "U2") (pin "11") (pinfunction "DQ6_11") (pintype "bidirectional"))
    )
    (net (code "46") (name "/MD7") (class "Default")
      (node (ref "U1") (pin "96") (pinfunction "MD7_96") (pintype "bidirectional"))
      (node (ref "U2") (pin "13") (pinfunction "DQ7_13") (pintype "bidirectional"))
    )
    (net (code "47") (name "/MD8") (class "Default")
      (node (ref "U1") (pin "97") (pinfunction "MD8_97") (pintype "bidirectional"))
      (node (ref "U2") (pin "74") (pinfunction "DQ8_74") (pintype "bidirectional"))
    )
    (net (code "48") (name "/MD9") (class "Default")
      (node (ref "U1") (pin "94") (pinfunction "MD9_94") (pintype "bidirectional"))
      (node (ref "U2") (pin "76") (pinfunction "DQ9_76") (pintype "bidirectional"))
    )
    (net (code "49") (name "/MD10") (class "Default")
      (node (ref "U1") (pin "95") (pinfunction "MD10_95") (pintype "bidirectional"))
      (node (ref "U2") (pin "77") (pinfunction "DQ10_77") (pintype "bidirectional"))
    )
    (net (code "50") (name "/MD11") (class "Default")
      (node (ref "U1") (pin "89") (pinfunction "MD11_89") (pintype "bidirectional"))
      (node (ref "U2") (pin "79") (pinfunction "DQ11_79") (pintype "bidirectional"))
    )
    (net (code "51") (name "/MD12") (class "Default")
      (node (ref "U1") (pin "87") (pinfunction "MD12_87") (pintype "bidirectional"))
      (node (ref "U2") (pin "80") (pinfunction "DQ12_80") (pintype "bidirectional"))
    )
    (net (code "52") (name "/MD13") (class "Default")
      (node (ref "U1") (pin "85") (pinfunction "MD13_85") (pintype "bidirectional"))
      (node (ref "U2") (pin "82") (pinfunction "DQ13_82") (pintype "bidirectional"))
    )
    (net (code "53") (name "/MD14") (class "Default")
      (node (ref "U1") (pin "81") (pinfunction "MD14_81") (pintype "bidirectional"))
      (node (ref "U2") (pin "83") (pinfunction "DQ14_83") (pintype "bidirectional"))
    )
    (net (code "54") (name "/MD15") (class "Default")
      (node (ref "U1") (pin "79") (pinfunction "MD15_79") (pintype "bidirectional"))
      (node (ref "U2") (pin "85") (pinfunction "DQ15_85") (pintype "bidirectional"))
    )
    (net (code "55") (name "/MD16") (class "Default")
      (node (ref "U1") (pin "131") (pinfunction "MD16_131") (pintype "bidirectional"))
      (node (ref "U2") (pin "31") (pinfunction "DQ16_31") (pintype "bidirectional"))
    )
    (net (code "56") (name "/MD17") (class "Default")
      (node (ref "U1") (pin "133") (pinfunction "MD17_133") (pintype "bidirectional"))
      (node (ref "U2") (pin "33") (pinfunction "DQ17_33") (pintype "bidirectional"))
    )
    (net (code "57") (name "/MD18") (class "Default")
      (node (ref "U1") (pin "137") (pinfunction "MD18_137") (pintype "bidirectional"))
      (node (ref "U2") (pin "34") (pinfunction "DQ18_34") (pintype "bidirectional"))
    )
    (net (code "58") (name "/MD19") (class "Default")
      (node (ref "U1") (pin "139") (pinfunction "MD19_139") (pintype "bidirectional"))
      (node (ref "U2") (pin "36") (pinfunction "DQ19_36") (pintype "bidirectional"))
    )
    (net (code "59") (name "/MD20") (class "Default")
      (node (ref "U1") (pin "141") (pinfunction "MD20_141") (pintype "bidirectional"))
      (node (ref "U2") (pin "37") (pinfunction "DQ20_37") (pintype "bidirectional"))
    )
    (net (code "60") (name "/MD21") (class "Default")
      (node (ref "U1") (pin "145") (pinfunction "MD21_145") (pintype "bidirectional"))
      (node (ref "U2") (pin "39") (pinfunction "DQ21_39") (pintype "bidirectional"))
    )
    (net (code "61") (name "/MD22") (class "Default")
      (node (ref "U1") (pin "149") (pinfunction "MD22_149") (pintype "bidirectional"))
      (node (ref "U2") (pin "40") (pinfunction "DQ22_40") (pintype "bidirectional"))
    )
    (net (code "62") (name "/MD23") (class "Default")
      (node (ref "U1") (pin "151") (pinfunction "MD23_151") (pintype "bidirectional"))
      (node (ref "U2") (pin "42") (pinfunction "DQ23_42") (pintype "bidirectional"))
    )
    (net (code "63") (name "/MD24") (class "Default")
      (node (ref "U1") (pin "152") (pinfunction "MD24_152") (pintype "bidirectional"))
      (node (ref "U2") (pin "45") (pinfunction "DQ24_45") (pintype "bidirectional"))
    )
    (net (code "64") (name "/MD25") (class "Default")
      (node (ref "U1") (pin "150") (pinfunction "MD25_150") (pintype "bidirectional"))
      (node (ref "U2") (pin "47") (pinfunction "DQ25_47") (pintype "bidirectional"))
    )
    (net (code "65") (name "/MD26") (class "Default")
      (node (ref "U1") (pin "146") (pinfunction "MD26_146") (pintype "bidirectional"))
      (node (ref "U2") (pin "48") (pinfunction "DQ26_48") (pintype "bidirectional"))
    )
    (net (code "66") (name "/MD27") (class "Default")
      (node (ref "U1") (pin "144") (pinfunction "MD27_144") (pintype "bidirectional"))
      (node (ref "U2") (pin "50") (pinfunction "DQ27_50") (pintype "bidirectional"))
    )
    (net (code "67") (name "/MD28") (class "Default")
      (node (ref "U1") (pin "140") (pinfunction "MD28_140") (pintype "bidirectional"))
      (node (ref "U2") (pin "51") (pinfunction "DQ28_51") (pintype "bidirectional"))
    )
    (net (code "68") (name "/MD29") (class "Default")
      (node (ref "U1") (pin "138") (pinfunction "MD29_138") (pintype "bidirectional"))
      (node (ref "U2") (pin "53") (pinfunction "DQ29_53") (pintype "bidirectional"))
    )
    (net (code "69") (name "/MD30") (class "Default")
      (node (ref "U1") (pin "134") (pinfunction "MD30_134") (pintype "bidirectional"))
      (node (ref "U2") (pin "54") (pinfunction "DQ30_54") (pintype "bidirectional"))
    )
    (net (code "70") (name "/MD31") (class "Default")
      (node (ref "U1") (pin "132") (pinfunction "MD31_132") (pintype "bidirectional"))
      (node (ref "U2") (pin "56") (pinfunction "DQ31_56") (pintype "bidirectional"))
    )
    (net (code "71") (name "/PCLK") (class "Default")
      (node (ref "U1") (pin "40") (pinfunction "PCLKIN_40") (pintype "bidirectional"))
      (node (ref "U5") (pin "10") (pinfunction "CLK0_10") (pintype "output"))
    )
    (net (code "72") (name "/R") (class "Default")
      (node (ref "J2") (pin "1") (pinfunction "1_1") (pintype "passive"))
      (node (ref "R3") (pin "1") (pinfunction "1_1") (pintype "passive"))
      (node (ref "R4") (pin "2") (pinfunction "2_2") (pintype "passive"))
    )
    (net (code "73") (name "/RAS#") (class "Default")
      (node (ref "U1") (pin "106") (pinfunction "RAS#_106") (pintype "bidirectional"))
      (node (ref "U2") (pin "19") (pinfunction "~{RAS}_19") (pintype "input"))
    )
    (net (code "74") (name "/ROUT") (class "Default")
      (node (ref "C56") (pin "1") (pinfunction "1_1") (pintype "passive"))
      (node (ref "FB1") (pin "1") (pinfunction "P$1_1") (pintype "bidirectional"))
      (node (ref "R18") (pin "1") (pinfunction "1_1") (pintype "passive"))
      (node (ref "U1") (pin "160") (pinfunction "AGPR_160") (pintype "bidirectional"))
    )
    (net (code "75") (name "/RTS") (class "Default")
      (node (ref "U6") (pin "14") (pinfunction "~{RTS}_14") (pintype "bidirectional"))
    )
    (net (code "76") (name "/R_VGA") (class "Default")
      (node (ref "C56") (pin "2") (pinfunction "2_2") (pintype "passive"))
      (node (ref "C59") (pin "1") (pinfunction "1_1") (pintype "passive"))
      (node (ref "FB1") (pin "2") (pinfunction "P$2_2") (pintype "bidirectional"))
      (node (ref "J3") (pin "1") (pinfunction "1_1") (pintype "passive"))
    )
    (net (code "77") (name "/S") (class "Default")
      (node (ref "C6") (pin "2") (pinfunction "2_2") (pintype "passive"))
      (node (ref "J2") (pin "7") (pinfunction "7_7") (pintype "passive"))
      (node (ref "R9") (pin "2") (pinfunction "2_2") (pintype "passive"))
    )
    (net (code "78") (name "/SCL") (class "Default")
      (node (ref "R23") (pin "2") (pinfunction "2_2") (pintype "passive"))
      (node (ref "U1") (pin "41") (pinfunction "SCLCK_41") (pintype "bidirectional"))
      (node (ref "U3") (pin "P$9") (pinfunction "GPIO5_P$9") (pintype "bidirectional"))
      (node (ref "U5") (pin "4") (pinfunction "SCL_4") (pintype "input"))
    )
    (net (code "79") (name "/SDA") (class "Default")
      (node (ref "R22") (pin "2") (pinfunction "2_2") (pintype "passive"))
      (node (ref "U1") (pin "42") (pinfunction "SCLDA_42") (pintype "bidirectional"))
      (node (ref "U3") (pin "P$12") (pinfunction "GPIO4_P$12") (pintype "bidirectional"))
      (node (ref "U5") (pin "5") (pinfunction "SDA_5") (pintype "bidirectional"))
    )
    (net (code "80") (name "/V") (class "Default")
      (node (ref "J3") (pin "9") (pinfunction "9_9") (pintype "passive"))
      (node (ref "R21") (pin "1") (pinfunction "1_1") (pintype "passive"))
    )
    (net (code "81") (name "/VS") (class "Default")
      (node (ref "C62") (pin "1") (pinfunction "1_1") (pintype "passive"))
      (node (ref "R21") (pin "2") (pinfunction "2_2") (pintype "passive"))
      (node (ref "U4") (pin "6") (pinfunction "O_6") (pintype "tri_state"))
    )
    (net (code "82") (name "/VSOUT") (class "Default")
      (node (ref "U1") (pin "2") (pinfunction "VSOUT_2") (pintype "bidirectional"))
      (node (ref "U4") (pin "5") (pinfunction "I_5") (pintype "input"))
    )
    (net (code "83") (name "/WE#") (class "Default")
      (node (ref "U1") (pin "99") (pinfunction "WE#_99") (pintype "bidirectional"))
      (node (ref "U2") (pin "17") (pinfunction "~{WE}_17") (pintype "passive"))
    )
    (net (code "84") (name "1.8V") (class "Default")
      (node (ref "C14") (pin "1") (pinfunction "1_1") (pintype "passive"))
      (node (ref "C15") (pin "1") (pinfunction "1_1") (pintype "passive"))
      (node (ref "C16") (pin "1") (pinfunction "1_1") (pintype "passive"))
      (node (ref "C17") (pin "1") (pinfunction "1_1") (pintype "passive"))
      (node (ref "C18") (pin "1") (pinfunction "1_1") (pintype "passive"))
      (node (ref "C19") (pin "1") (pinfunction "1_1") (pintype "passive"))
      (node (ref "C54") (pin "1") (pinfunction "1_1") (pintype "passive"))
      (node (ref "U1") (pin "102") (pinfunction "VDD2_102") (pintype "bidirectional"))
      (node (ref "U1") (pin "142") (pinfunction "VDD3_142") (pintype "bidirectional"))
      (node (ref "U1") (pin "16") (pinfunction "VDD_16") (pintype "bidirectional"))
      (node (ref "U8") (pin "4") (pinfunction "OUT_4") (pintype "bidirectional"))
    )
    (net (code "85") (name "GND") (class "Default")
      (node (ref "ANT1") (pin "P$1") (pinfunction "GND_P$1") (pintype "input"))
      (node (ref "C1") (pin "2") (pinfunction "2_2") (pintype "passive"))
      (node (ref "C10") (pin "1") (pinfunction "1_1") (pintype "passive"))
      (node (ref "C11") (pin "1") (pinfunction "1_1") (pintype "passive"))
      (node (ref "C12") (pin "2") (pinfunction "2_2") (pintype "passive"))
      (node (ref "C13") (pin "2") (pinfunction "2_2") (pintype "passive"))
      (node (ref "C14") (pin "2") (pinfunction "2_2") (pintype "passive"))
      (node (ref "C15") (pin "2") (pinfunction "2_2") (pintype "passive"))
      (node (ref "C16") (pin "2") (pinfunction "2_2") (pintype "passive"))
      (node (ref "C17") (pin "2") (pinfunction "2_2") (pintype "passive"))
      (node (ref "C18") (pin "2") (pinfunction "2_2") (pintype "passive"))
      (node (ref "C19") (pin "2") (pinfunction "2_2") (pintype "passive"))
      (node (ref "C2") (pin "2") (pinfunction "2_2") (pintype "passive"))
      (node (ref "C20") (pin "2") (pinfunction "2_2") (pintype "passive"))
      (node (ref "C21") (pin "2") (pinfunction "2_2") (pintype "passive"))
      (node (ref "C22") (pin "2") (pinfunction "2_2") (pintype "passive"))
      (node (ref "C23") (pin "2") (pinfunction "2_2") (pintype "passive"))
      (node (ref "C24") (pin "2") (pinfunction "2_2") (pintype "passive"))
      (node (ref "C25") (pin "2") (pinfunction "2_2") (pintype "passive"))
      (node (ref "C26") (pin "2") (pinfunction "2_2") (pintype "passive"))
      (node (ref "C27") (pin "2") (pinfunction "2_2") (pintype "passive"))
      (node (ref "C28") (pin "2") (pinfunction "2_2") (pintype "passive"))
      (node (ref "C29") (pin "2") (pinfunction "2_2") (pintype "passive"))
      (node (ref "C30") (pin "2") (pinfunction "2_2") (pintype "passive"))
      (node (ref "C31") (pin "2") (pinfunction "2_2") (pintype "passive"))
      (node (ref "C32") (pin "2") (pinfunction "2_2") (pintype "passive"))
      (node (ref "C33") (pin "2") (pinfunction "2_2") (pintype "passive"))
      (node (ref "C34") (pin "2") (pinfunction "2_2") (pintype "passive"))
      (node (ref "C35") (pin "2") (pinfunction "2_2") (pintype "passive"))
      (node (ref "C36") (pin "2") (pinfunction "2_2") (pintype "passive"))
      (node (ref "C37") (pin "2") (pinfunction "2_2") (pintype "passive"))
      (node (ref "C38") (pin "2") (pinfunction "2_2") (pintype "passive"))
      (node (ref "C39") (pin "2") (pinfunction "2_2") (pintype "passive"))
      (node (ref "C40") (pin "2") (pinfunction "2_2") (pintype "passive"))
      (node (ref "C41") (pin "2") (pinfunction "2_2") (pintype "passive"))
      (node (ref "C42") (pin "2") (pinfunction "2_2") (pintype "passive"))
      (node (ref "C43") (pin "2") (pinfunction "2_2") (pintype "passive"))
      (node (ref "C44") (pin "2") (pinfunction "2_2") (pintype "passive"))
      (node (ref "C45") (pin "2") (pinfunction "2_2") (pintype "passive"))
      (node (ref "C46") (pin "2") (pinfunction "2_2") (pintype "passive"))
      (node (ref "C47") (pin "2") (pinfunction "2_2") (pintype "passive"))
      (node (ref "C48") (pin "2") (pinfunction "2_2") (pintype "passive"))
      (node (ref "C49") (pin "2") (pinfunction "2_2") (pintype "passive"))
      (node (ref "C50") (pin "2") (pinfunction "2_2") (pintype "passive"))
      (node (ref "C51") (pin "2") (pinfunction "2_2") (pintype "passive"))
      (node (ref "C52") (pin "2") (pinfunction "2_2") (pintype "passive"))
      (node (ref "C53") (pin "2") (pinfunction "2_2") (pintype "passive"))
      (node (ref "C54") (pin "2") (pinfunction "2_2") (pintype "passive"))
      (node (ref "C55") (pin "2") (pinfunction "2_2") (pintype "passive"))
      (node (ref "C59") (pin "2") (pinfunction "2_2") (pintype "passive"))
      (node (ref "C60") (pin "2") (pinfunction "2_2") (pintype "passive"))
      (node (ref "C61") (pin "2") (pinfunction "2_2") (pintype "passive"))
      (node (ref "C62") (pin "2") (pinfunction "2_2") (pintype "passive"))
      (node (ref "C63") (pin "2") (pinfunction "2_2") (pintype "passive"))
      (node (ref "C9") (pin "1") (pinfunction "1_1") (pintype "passive"))
      (node (ref "J1") (pin "1") (pinfunction "GND_1") (pintype "passive"))
      (node (ref "J1") (pin "13") (pinfunction "GND_13") (pintype "passive"))
      (node (ref "J1") (pin "14") (pinfunction "GND_14") (pintype "passive"))
      (node (ref "J1") (pin "15") (pinfunction "GND_15") (pintype "passive"))
      (node (ref "J1") (pin "16") (pinfunction "GND_16") (pintype "passive"))
      (node (ref "J1") (pin "2") (pinfunction "GND_2") (pintype "passive"))
      (node (ref "J1") (pin "3") (pinfunction "GND_3") (pintype "passive"))
      (node (ref "J1") (pin "4") (pinfunction "GND_4") (pintype "passive"))
      (node (ref "J1") (pin "A1/B12") (pinfunction "GND_2_A1/B12") (pintype "passive"))
      (node (ref "J1") (pin "B1/A12") (pinfunction "GND_B1/A12") (pintype "passive"))
      (node (ref "J1") (pin "S_1_H1") (pinfunction "GND_S_1_H1") (pintype "passive"))
      (node (ref "J1") (pin "S_1_H2") (pinfunction "GND_S_1_H2") (pintype "passive"))
      (node (ref "J1") (pin "S_2_H1") (pinfunction "GND_S_2_H1") (pintype "passive"))
      (node (ref "J1") (pin "S_2_H2") (pinfunction "GND_S_2_H2") (pintype "passive"))
      (node (ref "J1") (pin "S_3_H1") (pinfunction "GND_S_3_H1") (pintype "passive"))
      (node (ref "J1") (pin "S_3_H2") (pinfunction "GND_S_3_H2") (pintype "passive"))
      (node (ref "J1") (pin "S_4_H1") (pinfunction "GND_S_4_H1") (pintype "passive"))
      (node (ref "J1") (pin "S_4_H2") (pinfunction "GND_S_4_H2") (pintype "passive"))
      (node (ref "J2") (pin "2") (pinfunction "2_2") (pintype "passive"))
      (node (ref "J2") (pin "4") (pinfunction "4_4") (pintype "passive"))
      (node (ref "J2") (pin "6") (pinfunction "6_6") (pintype "passive"))
      (node (ref "J3") (pin "10") (pinfunction "10_10") (pintype "passive"))
      (node (ref "J3") (pin "2") (pinfunction "2_2") (pintype "passive"))
      (node (ref "J3") (pin "4") (pinfunction "4_4") (pintype "passive"))
      (node (ref "J3") (pin "6") (pinfunction "6_6") (pintype "passive"))
      (node (ref "J3") (pin "8") (pinfunction "8_8") (pintype "passive"))
      (node (ref "J4") (pin "2") (pinfunction "2_2") (pintype "passive"))
      (node (ref "J5") (pin "2") (pinfunction "2_2") (pintype "passive"))
      (node (ref "R12") (pin "2") (pinfunction "2_2") (pintype "passive"))
      (node (ref "R13") (pin "2") (pinfunction "2_2") (pintype "passive"))
      (node (ref "R14") (pin "1") (pinfunction "1_1") (pintype "passive"))
      (node (ref "R16") (pin "2") (pinfunction "2_2") (pintype "passive"))
      (node (ref "R17") (pin "2") (pinfunction "2_2") (pintype "passive"))
      (node (ref "R18") (pin "2") (pinfunction "2_2") (pintype "passive"))
      (node (ref "R2") (pin "2") (pinfunction "2_2") (pintype "passive"))
      (node (ref "R28") (pin "2") (pinfunction "2_2") (pintype "passive"))
      (node (ref "R4") (pin "1") (pinfunction "1_1") (pintype "passive"))
      (node (ref "R6") (pin "1") (pinfunction "1_1") (pintype "passive"))
      (node (ref "R8") (pin "1") (pinfunction "1_1") (pintype "passive"))
      (node (ref "R9") (pin "1") (pinfunction "1_1") (pintype "passive"))
      (node (ref "U1") (pin "101") (pinfunction "VSS2_101") (pintype "bidirectional"))
      (node (ref "U1") (pin "105") (pinfunction "PVSS7_105") (pintype "bidirectional"))
      (node (ref "U1") (pin "113") (pinfunction "PVSS8_113") (pintype "bidirectional"))
      (node (ref "U1") (pin "122") (pinfunction "PAVS_122") (pintype "bidirectional"))
      (node (ref "U1") (pin "126") (pinfunction "PVSS9_126") (pintype "bidirectional"))
      (node (ref "U1") (pin "13") (pinfunction "PVSS2_13") (pintype "bidirectional"))
      (node (ref "U1") (pin "136") (pinfunction "PVSS10_136") (pintype "bidirectional"))
      (node (ref "U1") (pin "143") (pinfunction "VSS3_143") (pintype "bidirectional"))
      (node (ref "U1") (pin "148") (pinfunction "PVSS11_148") (pintype "bidirectional"))
      (node (ref "U1") (pin "153") (pinfunction "DVSS_153") (pintype "bidirectional"))
      (node (ref "U1") (pin "156") (pinfunction "DAVS_156") (pintype "bidirectional"))
      (node (ref "U1") (pin "17") (pinfunction "VSS_17") (pintype "bidirectional"))
      (node (ref "U1") (pin "25") (pinfunction "PVSS3_25") (pintype "bidirectional"))
      (node (ref "U1") (pin "35") (pinfunction "PVSS4_35") (pintype "bidirectional"))
      (node (ref "U1") (pin "43") (pinfunction "SCLSA_43") (pintype "bidirectional"))
      (node (ref "U1") (pin "5") (pinfunction "PVSS_5") (pintype "bidirectional"))
      (node (ref "U1") (pin "50") (pinfunction "AVS_PLL_50") (pintype "bidirectional"))
      (node (ref "U1") (pin "53") (pinfunction "AVS_REF_53") (pintype "bidirectional"))
      (node (ref "U1") (pin "56") (pinfunction "AVS_R_56") (pintype "bidirectional"))
      (node (ref "U1") (pin "58") (pinfunction "AVS_R2_58") (pintype "bidirectional"))
      (node (ref "U1") (pin "63") (pinfunction "AVS_G_63") (pintype "bidirectional"))
      (node (ref "U1") (pin "66") (pinfunction "AVS_G2_66") (pintype "bidirectional"))
      (node (ref "U1") (pin "70") (pinfunction "AVS_B_70") (pintype "bidirectional"))
      (node (ref "U1") (pin "72") (pinfunction "AVS_B2_72") (pintype "bidirectional"))
      (node (ref "U1") (pin "74") (pinfunction "AVS_B3_74") (pintype "bidirectional"))
      (node (ref "U1") (pin "83") (pinfunction "PVSS5_83") (pintype "bidirectional"))
      (node (ref "U1") (pin "93") (pinfunction "PVSS6_93") (pintype "bidirectional"))
      (node (ref "U2") (pin "12") (pinfunction "VSSQ_3_12") (pintype "power_in"))
      (node (ref "U2") (pin "20") (pinfunction "~{CS}_20") (pintype "passive"))
      (node (ref "U2") (pin "32") (pinfunction "VSSQ_4_32") (pintype "power_in"))
      (node (ref "U2") (pin "38") (pinfunction "VSSQ_5_38") (pintype "power_in"))
      (node (ref "U2") (pin "44") (pinfunction "VSS_2_44") (pintype "power_in"))
      (node (ref "U2") (pin "46") (pinfunction "VSSQ_6_46") (pintype "power_in"))
      (node (ref "U2") (pin "52") (pinfunction "VSSQ_7_52") (pintype "power_in"))
      (node (ref "U2") (pin "58") (pinfunction "VSS_3_58") (pintype "power_in"))
      (node (ref "U2") (pin "6") (pinfunction "VSSQ_2_6") (pintype "power_in"))
      (node (ref "U2") (pin "72") (pinfunction "VSS_4_72") (pintype "power_in"))
      (node (ref "U2") (pin "78") (pinfunction "VSSQ_8_78") (pintype "power_in"))
      (node (ref "U2") (pin "84") (pinfunction "VSSQ_84") (pintype "power_in"))
      (node (ref "U2") (pin "86") (pinfunction "VSS_86") (pintype "power_in"))
      (node (ref "U3") (pin "P$17") (pinfunction "GND_P$17") (pintype "bidirectional"))
      (node (ref "U3") (pin "P$18") (pinfunction "GND_P$18") (pintype "bidirectional"))
      (node (ref "U3") (pin "P$19") (pinfunction "GND_P$19") (pintype "bidirectional"))
      (node (ref "U3") (pin "P$20") (pinfunction "GND_P$20") (pintype "bidirectional"))
      (node (ref "U3") (pin "P$5") (pinfunction "GND_P$5") (pintype "bidirectional"))
      (node (ref "U4") (pin "1") (pinfunction "OE_1") (pintype "input"))
      (node (ref "U4") (pin "4") (pinfunction "OE_4") (pintype "input"))
      (node (ref "U4") (pin "7") (pinfunction "GND_7") (pintype "power_in"))
      (node (ref "U5") (pin "8") (pinfunction "GND_8") (pintype "power_in"))
      (node (ref "U6") (pin "1") (pinfunction "GND_1") (pintype "bidirectional"))
      (node (ref "U7") (pin "10") (pinfunction "MODE_10") (pintype "input"))
      (node (ref "U7") (pin "11") (pinfunction "VSEL_11") (pintype "input"))
      (node (ref "U7") (pin "3") (pinfunction "GND_3") (pintype "power_in"))
      (node (ref "U7") (pin "4") (pinfunction "FB2_4") (pintype "open_collector"))
      (node (ref "U7") (pin "7") (pinfunction "PG_7") (pintype "open_collector"))
      (node (ref "U8") (pin "2") (pinfunction "GND_2") (pintype "bidirectional"))
      (node (ref "U8") (pin "7") (pinfunction "EP_7") (pintype "bidirectional"))
    )
    (net (code "86") (name "Net-(ANT1-ANT)") (class "Default")
      (node (ref "ANT1") (pin "P$2") (pinfunction "ANT_P$2") (pintype "input"))
      (node (ref "U3") (pin "P$4") (pinfunction "ANT_P$4") (pintype "bidirectional"))
    )
    (net (code "87") (name "Net-(C3-Pad1)") (class "Default")
      (node (ref "C3") (pin "1") (pinfunction "1_1") (pintype "passive"))
      (node (ref "R3") (pin "2") (pinfunction "2_2") (pintype "passive"))
    )
    (net (code "88") (name "Net-(C4-Pad1)") (class "Default")
      (node (ref "C4") (pin "1") (pinfunction "1_1") (pintype "passive"))
      (node (ref "R5") (pin "2") (pinfunction "2_2") (pintype "passive"))
    )
    (net (code "89") (name "Net-(C5-Pad1)") (class "Default")
      (node (ref "C5") (pin "1") (pinfunction "1_1") (pintype "passive"))
      (node (ref "R7") (pin "2") (pinfunction "2_2") (pintype "passive"))
    )
    (net (code "90") (name "Net-(C7-Pad1)") (class "Default")
      (node (ref "C7") (pin "1") (pinfunction "1_1") (pintype "passive"))
      (node (ref "R10") (pin "1") (pinfunction "1_1") (pintype "passive"))
    )
    (net (code "91") (name "Net-(J1-CC1)") (class "Default")
      (node (ref "J1") (pin "A5") (pinfunction "CC1_A5") (pintype "bidirectional"))
      (node (ref "R12") (pin "1") (pinfunction "1_1") (pintype "passive"))
    )
    (net (code "92") (name "Net-(J1-CC2)") (class "Default")
      (node (ref "J1") (pin "B5") (pinfunction "CC2_B5") (pintype "bidirectional"))
      (node (ref "R13") (pin "1") (pinfunction "1_1") (pintype "passive"))
    )
    (net (code "93") (name "Net-(LED1-PadA)") (class "Default")
      (node (ref "LED1") (pin "A") (pinfunction "A_A") (pintype "passive"))
      (node (ref "R24") (pin "2") (pinfunction "2_2") (pintype "passive"))
    )
    (net (code "94") (name "Net-(LED2-PadA)") (class "Default")
      (node (ref "LED2") (pin "A") (pinfunction "A_A") (pintype "passive"))
      (node (ref "R25") (pin "2") (pinfunction "2_2") (pintype "passive"))
    )
    (net (code "95") (name "Net-(U1-B1)") (class "Default")
      (node (ref "C5") (pin "2") (pinfunction "2_2") (pintype "passive"))
      (node (ref "U1") (pin "71") (pinfunction "B1_71") (pintype "bidirectional"))
    )
    (net (code "96") (name "Net-(U1-FILT)") (class "Default")
      (node (ref "C8") (pin "1") (pinfunction "1_1") (pintype "passive"))
      (node (ref "R10") (pin "2") (pinfunction "2_2") (pintype "passive"))
      (node (ref "U1") (pin "49") (pinfunction "FILT_49") (pintype "bidirectional"))
    )
    (net (code "97") (name "Net-(U1-G1)") (class "Default")
      (node (ref "C4") (pin "2") (pinfunction "2_2") (pintype "passive"))
      (node (ref "U1") (pin "65") (pinfunction "G1_65") (pintype "bidirectional"))
    )
    (net (code "98") (name "Net-(U1-IREF)") (class "Default")
      (node (ref "R2") (pin "1") (pinfunction "1_1") (pintype "passive"))
      (node (ref "U1") (pin "155") (pinfunction "IREF_155") (pintype "bidirectional"))
    )
    (net (code "99") (name "Net-(U1-R1)") (class "Default")
      (node (ref "C3") (pin "2") (pinfunction "2_2") (pintype "passive"))
      (node (ref "U1") (pin "57") (pinfunction "R1_57") (pintype "bidirectional"))
    )
    (net (code "100") (name "Net-(U1-REFBP)") (class "Default")
      (node (ref "C9") (pin "2") (pinfunction "2_2") (pintype "passive"))
      (node (ref "U1") (pin "52") (pinfunction "REFBP_52") (pintype "bidirectional"))
    )
    (net (code "101") (name "Net-(U1-RSTN)") (class "Default")
      (node (ref "R1") (pin "2") (pinfunction "2_2") (pintype "passive"))
      (node (ref "U1") (pin "75") (pinfunction "RSTN_75") (pintype "bidirectional"))
    )
    (net (code "102") (name "Net-(U1-SOG1)") (class "Default")
      (node (ref "C6") (pin "1") (pinfunction "1_1") (pintype "passive"))
      (node (ref "U1") (pin "64") (pinfunction "SOG1_64") (pintype "bidirectional"))
    )
    (net (code "103") (name "Net-(U1-XTIN)") (class "Default")
      (node (ref "C11") (pin "2") (pinfunction "2_2") (pintype "passive"))
      (node (ref "R11") (pin "2") (pinfunction "2_2") (pintype "passive"))
      (node (ref "U1") (pin "124") (pinfunction "XTIN_124") (pintype "bidirectional"))
      (node (ref "Y1") (pin "3") (pinfunction "2_3") (pintype "passive"))
    )
    (net (code "104") (name "Net-(U1-XTOUT)") (class "Default")
      (node (ref "C10") (pin "2") (pinfunction "2_2") (pintype "passive"))
      (node (ref "R11") (pin "1") (pinfunction "1_1") (pintype "passive"))
      (node (ref "U1") (pin "125") (pinfunction "XTOUT_125") (pintype "bidirectional"))
      (node (ref "Y1") (pin "1") (pinfunction "1_1") (pintype "passive"))
    )
    (net (code "105") (name "Net-(U5-XA)") (class "Default")
      (node (ref "U5") (pin "2") (pinfunction "XA_2") (pintype "input"))
      (node (ref "Y2") (pin "3") (pinfunction "2_3") (pintype "passive"))
    )
    (net (code "106") (name "Net-(U5-XB)") (class "Default")
      (node (ref "U5") (pin "3") (pinfunction "XB_3") (pintype "input"))
      (node (ref "Y2") (pin "1") (pinfunction "1_1") (pintype "passive"))
    )
    (net (code "107") (name "Net-(U7-FB)") (class "Default")
      (node (ref "R14") (pin "2") (pinfunction "2_2") (pintype "passive"))
      (node (ref "R15") (pin "1") (pinfunction "1_1") (pintype "passive"))
      (node (ref "U7") (pin "5") (pinfunction "FB_5") (pintype "input"))
    )
    (net (code "108") (name "Net-(U7-SW)") (class "Default")
      (node (ref "L1") (pin "1") (pinfunction "1_1") (pintype "bidirectional"))
      (node (ref "U7") (pin "2") (pinfunction "SW_2") (pintype "power_in"))
    )
    (net (code "109") (name "Net-(U7-VOS)") (class "Default")
      (node (ref "C35") (pin "1") (pinfunction "1_1") (pintype "passive"))
      (node (ref "C36") (pin "1") (pinfunction "1_1") (pintype "passive"))
      (node (ref "L1") (pin "2") (pinfunction "2_2") (pintype "bidirectional"))
      (node (ref "R15") (pin "2") (pinfunction "2_2") (pintype "passive"))
      (node (ref "R19") (pin "1") (pinfunction "1_1") (pintype "passive"))
      (node (ref "U7") (pin "6") (pinfunction "VOS_6") (pintype "input"))
    )
    (net (code "110") (name "unconnected-(J1-SBU1-PadA8)") (class "Default")
      (node (ref "J1") (pin "A8") (pinfunction "SBU1_A8") (pintype "bidirectional"))
    )
    (net (code "111") (name "unconnected-(J1-SBU2-PadB8)") (class "Default")
      (node (ref "J1") (pin "B8") (pinfunction "SBU2_B8") (pintype "bidirectional"))
    )
    (net (code "112") (name "unconnected-(U1-ASVM-Pad154)") (class "Default")
      (node (ref "U1") (pin "154") (pinfunction "ASVM_154") (pintype "bidirectional"))
    )
    (net (code "113") (name "unconnected-(U1-B0-Pad69)") (class "Default")
      (node (ref "U1") (pin "69") (pinfunction "B0_69") (pintype "bidirectional"))
    )
    (net (code "114") (name "unconnected-(U1-B2-Pad73)") (class "Default")
      (node (ref "U1") (pin "73") (pinfunction "B2_73") (pintype "bidirectional"))
    )
    (net (code "115") (name "unconnected-(U1-CLKOUT-Pad4)") (class "Default")
      (node (ref "U1") (pin "4") (pinfunction "CLKOUT_4") (pintype "bidirectional"))
    )
    (net (code "116") (name "unconnected-(U1-G0-Pad62)") (class "Default")
      (node (ref "U1") (pin "62") (pinfunction "G0_62") (pintype "bidirectional"))
    )
    (net (code "117") (name "unconnected-(U1-G2-Pad67)") (class "Default")
      (node (ref "U1") (pin "67") (pinfunction "G2_67") (pintype "bidirectional"))
    )
    (net (code "118") (name "unconnected-(U1-GPIO-Pad76)") (class "Default")
      (node (ref "U1") (pin "76") (pinfunction "GPIO_76") (pintype "bidirectional"))
    )
    (net (code "119") (name "unconnected-(U1-HALF-Pad77)") (class "Default")
      (node (ref "U1") (pin "77") (pinfunction "HALF_77") (pintype "bidirectional"))
    )
    (net (code "120") (name "unconnected-(U1-HBOUT-Pad6)") (class "Default")
      (node (ref "U1") (pin "6") (pinfunction "HBOUT_6") (pintype "bidirectional"))
    )
    (net (code "121") (name "unconnected-(U1-HSIN1-Pad44)") (class "Default")
      (node (ref "U1") (pin "44") (pinfunction "HSIN1_44") (pintype "bidirectional"))
    )
    (net (code "122") (name "unconnected-(U1-HSIN2-Pad46)") (class "Default")
      (node (ref "U1") (pin "46") (pinfunction "HSIN2_46") (pintype "bidirectional"))
    )
    (net (code "123") (name "unconnected-(U1-R0-Pad55)") (class "Default")
      (node (ref "U1") (pin "55") (pinfunction "R0_55") (pintype "bidirectional"))
    )
    (net (code "124") (name "unconnected-(U1-R2-Pad59)") (class "Default")
      (node (ref "U1") (pin "59") (pinfunction "R2_59") (pintype "bidirectional"))
    )
    (net (code "125") (name "unconnected-(U1-SOG0-Pad61)") (class "Default")
      (node (ref "U1") (pin "61") (pinfunction "SOG0_61") (pintype "bidirectional"))
    )
    (net (code "126") (name "unconnected-(U1-VB0-Pad8)") (class "Default")
      (node (ref "U1") (pin "8") (pinfunction "VB0_8") (pintype "bidirectional"))
    )
    (net (code "127") (name "unconnected-(U1-VB1-Pad9)") (class "Default")
      (node (ref "U1") (pin "9") (pinfunction "VB1_9") (pintype "bidirectional"))
    )
    (net (code "128") (name "unconnected-(U1-VB2-Pad10)") (class "Default")
      (node (ref "U1") (pin "10") (pinfunction "VB2_10") (pintype "bidirectional"))
    )
    (net (code "129") (name "unconnected-(U1-VB4-Pad14)") (class "Default")
      (node (ref "U1") (pin "14") (pinfunction "VB4_14") (pintype "bidirectional"))
    )
    (net (code "130") (name "unconnected-(U1-VB5-Pad15)") (class "Default")
      (node (ref "U1") (pin "15") (pinfunction "VB5_15") (pintype "bidirectional"))
    )
    (net (code "131") (name "unconnected-(U1-VB6-Pad18)") (class "Default")
      (node (ref "U1") (pin "18") (pinfunction "VB6_18") (pintype "bidirectional"))
    )
    (net (code "132") (name "unconnected-(U1-VB7-Pad19)") (class "Default")
      (node (ref "U1") (pin "19") (pinfunction "VB7_19") (pintype "bidirectional"))
    )
    (net (code "133") (name "unconnected-(U1-VBOUT-Pad7)") (class "Default")
      (node (ref "U1") (pin "7") (pinfunction "VBOUT_7") (pintype "bidirectional"))
    )
    (net (code "134") (name "unconnected-(U1-VG0-Pad20)") (class "Default")
      (node (ref "U1") (pin "20") (pinfunction "VG0_20") (pintype "bidirectional"))
    )
    (net (code "135") (name "unconnected-(U1-VG1-Pad21)") (class "Default")
      (node (ref "U1") (pin "21") (pinfunction "VG1_21") (pintype "bidirectional"))
    )
    (net (code "136") (name "unconnected-(U1-VG2-Pad22)") (class "Default")
      (node (ref "U1") (pin "22") (pinfunction "VG2_22") (pintype "bidirectional"))
    )
    (net (code "137") (name "unconnected-(U1-VG3-Pad23)") (class "Default")
      (node (ref "U1") (pin "23") (pinfunction "VG3_23") (pintype "bidirectional"))
    )
    (net (code "138") (name "unconnected-(U1-VG4-Pad26)") (class "Default")
      (node (ref "U1") (pin "26") (pinfunction "VG4_26") (pintype "bidirectional"))
    )
    (net (code "139") (name "unconnected-(U1-VG5-Pad27)") (class "Default")
      (node (ref "U1") (pin "27") (pinfunction "VG5_27") (pintype "bidirectional"))
    )
    (net (code "140") (name "unconnected-(U1-VG6-Pad28)") (class "Default")
      (node (ref "U1") (pin "28") (pinfunction "VG6_28") (pintype "bidirectional"))
    )
    (net (code "141") (name "unconnected-(U1-VG7-Pad29)") (class "Default")
      (node (ref "U1") (pin "29") (pinfunction "VG7_29") (pintype "bidirectional"))
    )
    (net (code "142") (name "unconnected-(U1-VR0-Pad30)") (class "Default")
      (node (ref "U1") (pin "30") (pinfunction "VR0_30") (pintype "bidirectional"))
    )
    (net (code "143") (name "unconnected-(U1-VR1-Pad31)") (class "Default")
      (node (ref "U1") (pin "31") (pinfunction "VR1_31") (pintype "bidirectional"))
    )
    (net (code "144") (name "unconnected-(U1-VR2-Pad32)") (class "Default")
      (node (ref "U1") (pin "32") (pinfunction "VR2_32") (pintype "bidirectional"))
    )
    (net (code "145") (name "unconnected-(U1-VR3-Pad33)") (class "Default")
      (node (ref "U1") (pin "33") (pinfunction "VR3_33") (pintype "bidirectional"))
    )
    (net (code "146") (name "unconnected-(U1-VR4-Pad36)") (class "Default")
      (node (ref "U1") (pin "36") (pinfunction "VR4_36") (pintype "bidirectional"))
    )
    (net (code "147") (name "unconnected-(U1-VR5-Pad37)") (class "Default")
      (node (ref "U1") (pin "37") (pinfunction "VR5_37") (pintype "bidirectional"))
    )
    (net (code "148") (name "unconnected-(U1-VR6-Pad38)") (class "Default")
      (node (ref "U1") (pin "38") (pinfunction "VR6_38") (pintype "bidirectional"))
    )
    (net (code "149") (name "unconnected-(U1-VR7-Pad39)") (class "Default")
      (node (ref "U1") (pin "39") (pinfunction "VR7_39") (pintype "bidirectional"))
    )
    (net (code "150") (name "unconnected-(U1-VSIN1-Pad45)") (class "Default")
      (node (ref "U1") (pin "45") (pinfunction "VSIN1_45") (pintype "bidirectional"))
    )
    (net (code "151") (name "unconnected-(U1-VSIN2-Pad47)") (class "Default")
      (node (ref "U1") (pin "47") (pinfunction "VSIN2_47") (pintype "bidirectional"))
    )
    (net (code "152") (name "unconnected-(U2-NC-Pad73)") (class "Default")
      (node (ref "U2") (pin "73") (pinfunction "NC_73") (pintype "no_connect"))
    )
    (net (code "153") (name "unconnected-(U2-NC_2-Pad14)") (class "Default")
      (node (ref "U2") (pin "14") (pinfunction "NC_2_14") (pintype "no_connect"))
    )
    (net (code "154") (name "unconnected-(U2-NC_3-Pad21)") (class "Default")
      (node (ref "U2") (pin "21") (pinfunction "NC_3_21") (pintype "no_connect"))
    )
    (net (code "155") (name "unconnected-(U2-NC_4-Pad30)") (class "Default")
      (node (ref "U2") (pin "30") (pinfunction "NC_4_30") (pintype "no_connect"))
    )
    (net (code "156") (name "unconnected-(U2-NC_5-Pad57)") (class "Default")
      (node (ref "U2") (pin "57") (pinfunction "NC_5_57") (pintype "no_connect"))
    )
    (net (code "157") (name "unconnected-(U2-NC_6-Pad69)") (class "Default")
      (node (ref "U2") (pin "69") (pinfunction "NC_6_69") (pintype "no_connect"))
    )
    (net (code "158") (name "unconnected-(U2-NC_7-Pad70)") (class "Default")
      (node (ref "U2") (pin "70") (pinfunction "NC_7_70") (pintype "no_connect"))
    )
    (net (code "159") (name "unconnected-(U3-GPIO13-PadP$14)") (class "Default")
      (node (ref "U3") (pin "P$14") (pinfunction "GPIO13_P$14") (pintype "bidirectional"))
    )
    (net (code "160") (name "unconnected-(U3-GPIO14-PadP$16)") (class "Default")
      (node (ref "U3") (pin "P$16") (pinfunction "GPIO14_P$16") (pintype "bidirectional"))
    )
    (net (code "161") (name "unconnected-(U3-GPIO16-PadP$1)") (class "Default")
      (node (ref "U3") (pin "P$1") (pinfunction "GPIO16_P$1") (pintype "bidirectional"))
    )
    (net (code "162") (name "unconnected-(U5-CLK1-Pad9)") (class "Default")
      (node (ref "U5") (pin "9") (pinfunction "CLK1_9") (pintype "output"))
    )
    (net (code "163") (name "unconnected-(U5-CLK2-Pad6)") (class "Default")
      (node (ref "U5") (pin "6") (pinfunction "CLK2_6") (pintype "output"))
    )
    (net (code "164") (name "unconnected-(U6-R232-Pad15)") (class "Default")
      (node (ref "U6") (pin "15") (pinfunction "R232_15") (pintype "bidirectional"))
    )
    (net (code "165") (name "unconnected-(U6-~{CTS}-Pad9)") (class "Default")
      (node (ref "U6") (pin "9") (pinfunction "~{CTS}_9") (pintype "bidirectional"))
    )
    (net (code "166") (name "unconnected-(U6-~{DCD}-Pad12)") (class "Default")
      (node (ref "U6") (pin "12") (pinfunction "~{DCD}_12") (pintype "bidirectional"))
    )
    (net (code "167") (name "unconnected-(U6-~{DSR}-Pad10)") (class "Default")
      (node (ref "U6") (pin "10") (pinfunction "~{DSR}_10") (pintype "bidirectional"))
    )
    (net (code "168") (name "unconnected-(U6-~{RI}-Pad11)") (class "Default")
      (node (ref "U6") (pin "11") (pinfunction "~{RI}_11") (pintype "bidirectional"))
    )
    (net (code "169") (name "unconnected-(U7-SS_TR-Pad9)") (class "Default")
      (node (ref "U7") (pin "9") (pinfunction "SS_TR_9") (pintype "input"))
    )
    (net (code "170") (name "unconnected-(U8-NC-Pad5)") (class "Default")
      (node (ref "U8") (pin "5") (pinfunction "NC_5") (pintype "no_connect"))
    )
    (net (code "171") (name "unconnected-(U8-PG-Pad3)") (class "Default")
      (node (ref "U8") (pin "3") (pinfunction "PG_3") (pintype "bidirectional"))
    )
  )
)
